# Sheet2.net
KiCad netlist of a schematic drawn in Altium Designer
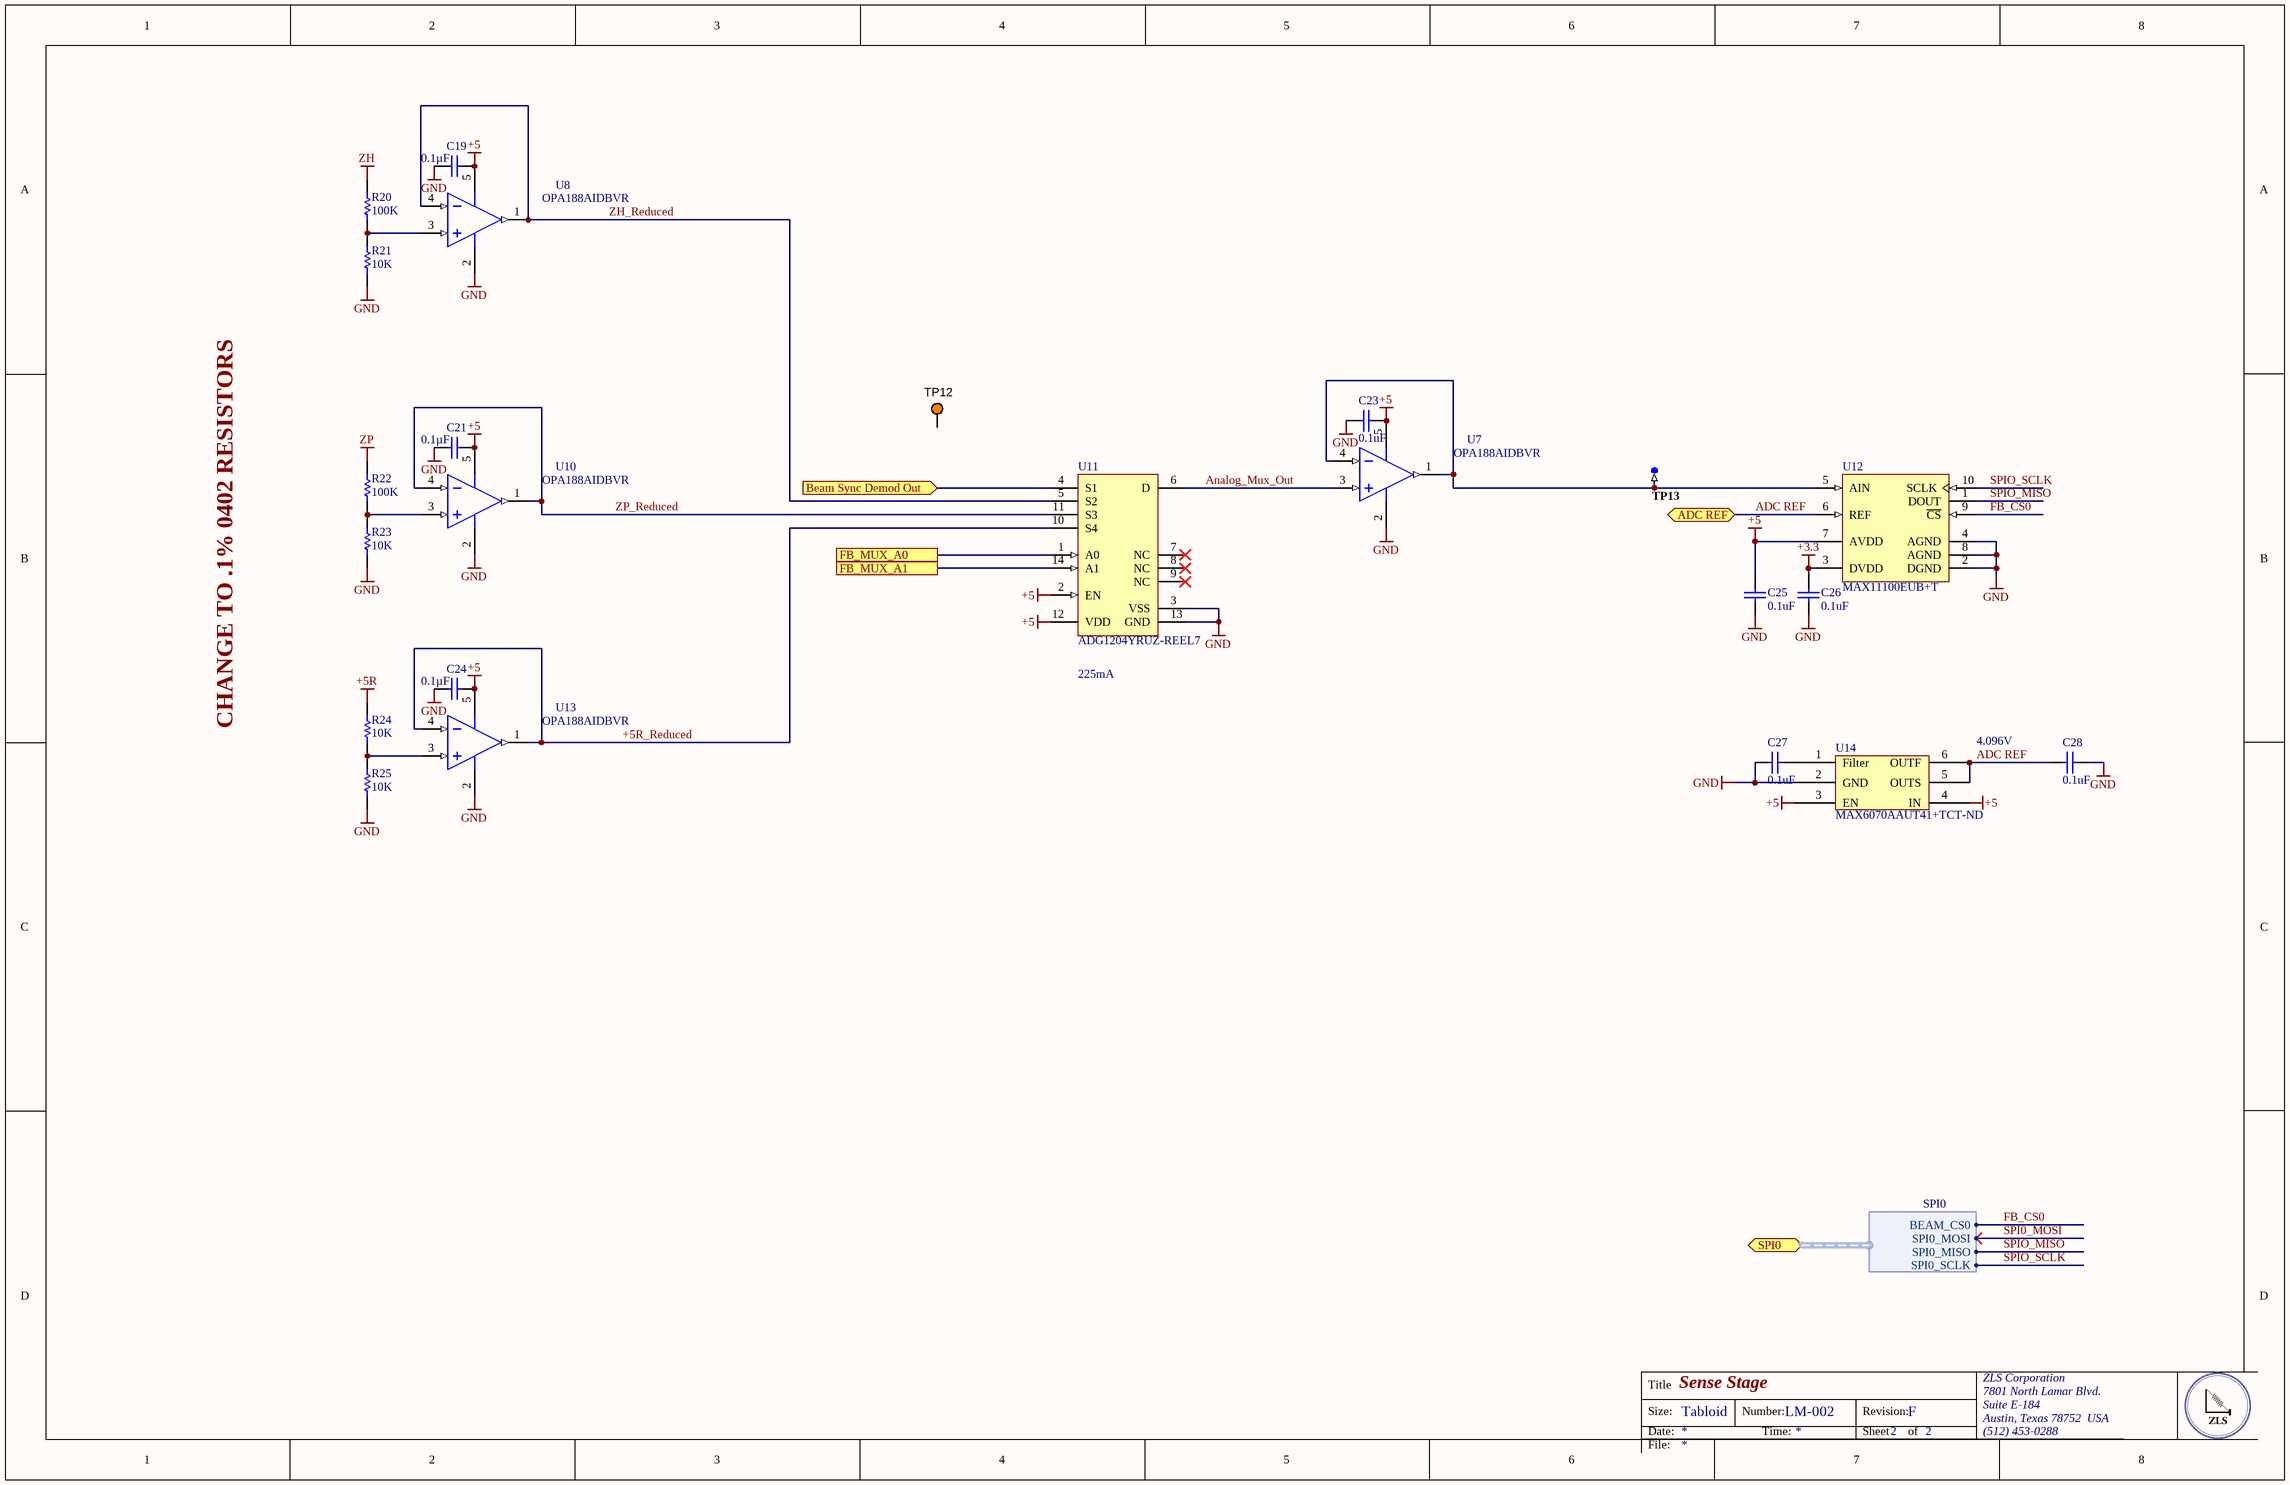
[diagram p0: Sheet2.SchDoc]

(export (version "E")
  (design (tool "Eeschema 10.0.6"))
  (components
    (comp (ref "C19")
      (value "CAP CER 0.1UF 25V X7R 0805")
      (footprint "CAPC0805(2012)145_N")
      (fields
        (field (name "MANUFACTURER") "Murata Electronics North America")
        (field (name "MANUFACTURER PART NUMBER") "GRM21BR71E104KA01L")
        (field (name "CAPACITANCE") "0.1µF")
        (field (name "TOLERANCE") "±10%")
      )
      (libsource (lib "Altium Content Vault") (part "CMP-1036-04795-1"))
    )
    (comp (ref "C21")
      (value "CAP CER 0.1UF 25V X7R 0805")
      (footprint "CAPC0805(2012)145_N")
      (fields
        (field (name "MANUFACTURER") "Murata Electronics North America")
        (field (name "MANUFACTURER PART NUMBER") "GRM21BR71E104KA01L")
        (field (name "CAPACITANCE") "0.1µF")
        (field (name "TOLERANCE") "±10%")
      )
      (libsource (lib "Altium Content Vault") (part "CMP-1036-04795-1"))
    )
    (comp (ref "C23")
      (value "0.1uF")
      (footprint "CAPC0402(1005)60_L")
      (description "CAP CER 0.1UF 10V X7R 0402")
      (fields
        (field (name "MANUFACTURER") "Murata Electronics North America")
        (field (name "MANUFACTURER PART NUMBER") "GRM155R71A104KA01D")
      )
      (libsource (lib "Altium Content Vault") (part "CMP-1034-00252-1"))
    )
    (comp (ref "C24")
      (value "CAP CER 0.1UF 25V X7R 0805")
      (footprint "CAPC0805(2012)145_N")
      (fields
        (field (name "MANUFACTURER") "Murata Electronics North America")
        (field (name "MANUFACTURER PART NUMBER") "GRM21BR71E104KA01L")
        (field (name "CAPACITANCE") "0.1µF")
        (field (name "TOLERANCE") "±10%")
      )
      (libsource (lib "Altium Content Vault") (part "CMP-1036-04795-1"))
    )
    (comp (ref "C25")
      (value "0.1uF")
      (footprint "CAPC0402(1005)60_L")
      (description "CAP CER 0.1UF 10V X7R 0402")
      (fields
        (field (name "MANUFACTURER") "Murata Electronics North America")
        (field (name "MANUFACTURER PART NUMBER") "GRM155R71A104KA01D")
      )
      (libsource (lib "Altium Content Vault") (part "CMP-1034-00252-1"))
    )
    (comp (ref "C26")
      (value "0.1uF")
      (footprint "CAPC0402(1005)60_L")
      (description "CAP CER 0.1UF 10V X7R 0402")
      (fields
        (field (name "MANUFACTURER") "Murata Electronics North America")
        (field (name "MANUFACTURER PART NUMBER") "GRM155R71A104KA01D")
      )
      (libsource (lib "Altium Content Vault") (part "CMP-1034-00252-1"))
    )
    (comp (ref "C27")
      (value "0.1uF")
      (footprint "CAPC0402(1005)60_L")
      (description "CAP CER 0.1UF 10V X7R 0402")
      (fields
        (field (name "MANUFACTURER") "Murata Electronics North America")
        (field (name "MANUFACTURER PART NUMBER") "GRM155R71A104KA01D")
      )
      (libsource (lib "Altium Content Vault") (part "CMP-1034-00252-1"))
    )
    (comp (ref "C28")
      (value "0.1uF")
      (footprint "CAPC0402(1005)60_L")
      (description "CAP CER 0.1UF 10V X7R 0402")
      (fields
        (field (name "MANUFACTURER") "Murata Electronics North America")
        (field (name "MANUFACTURER PART NUMBER") "GRM155R71A104KA01D")
      )
      (libsource (lib "Altium Content Vault") (part "CMP-1034-00252-1"))
    )
    (comp (ref "R20")
      (value "100K")
      (footprint "RESC0805(2012)_L")
      (description "RES SMD 100K OHM 1% 1/8W 0805")
      (fields
        (field (name "MANUFACTURER") "Vishay Dale")
        (field (name "MANUFACTURER PART NUMBER") "RCA0805100KFKEA")
      )
      (libsource (lib "Altium Content Vault") (part "CMP-1013-00215-1"))
    )
    (comp (ref "R21")
      (value "10K")
      (footprint "RESC0805(2012)_L")
      (description "RES SMD 10K OHM 1% 1/8W 0805")
      (fields
        (field (name "MANUFACTURER") "Vishay Dale")
        (field (name "MANUFACTURER PART NUMBER") "CRCW080510K0FKEA")
      )
      (libsource (lib "Altium Content Vault") (part "CMP-1013-00215-1"))
    )
    (comp (ref "R22")
      (value "100K")
      (footprint "RESC0805(2012)_L")
      (description "RES SMD 100K OHM 1% 1/8W 0805")
      (fields
        (field (name "MANUFACTURER") "Vishay Dale")
        (field (name "MANUFACTURER PART NUMBER") "RCA0805100KFKEA")
      )
      (libsource (lib "Altium Content Vault") (part "CMP-1013-00215-1"))
    )
    (comp (ref "R23")
      (value "10K")
      (footprint "RESC0805(2012)_L")
      (description "RES SMD 10K OHM 1% 1/8W 0805")
      (fields
        (field (name "MANUFACTURER") "Vishay Dale")
        (field (name "MANUFACTURER PART NUMBER") "CRCW080510K0FKEA")
      )
      (libsource (lib "Altium Content Vault") (part "CMP-1013-00215-1"))
    )
    (comp (ref "R24")
      (value "10K")
      (footprint "RESC0805(2012)_L")
      (description "RES SMD 10K OHM 1% 1/8W 0805")
      (fields
        (field (name "MANUFACTURER") "Vishay Dale")
        (field (name "MANUFACTURER PART NUMBER") "CRCW080510K0FKEA")
      )
      (libsource (lib "Altium Content Vault") (part "CMP-1013-00215-1"))
    )
    (comp (ref "R25")
      (value "10K")
      (footprint "RESC0805(2012)_L")
      (description "RES SMD 10K OHM 1% 1/8W 0805")
      (fields
        (field (name "MANUFACTURER") "Vishay Dale")
        (field (name "MANUFACTURER PART NUMBER") "CRCW080510K0FKEA")
      )
      (libsource (lib "Altium Content Vault") (part "CMP-1013-00215-1"))
    )
    (comp (ref "TP12")
      (value "5003")
      (footprint "KSTN-5003")
      (description "Test Point, Orange, 1-Pin THD, RoHS")
      (libsource (lib "Altium Content Vault") (part "CMP-1672-00009-1"))
    )
    (comp (ref "TP13")
      (value "TP-SM-C-100")
      (footprint "TP-SM-C-100")
      (description "Test Point, Surface Mount, Circular, Pad Diameter 1 mm")
      (fields (field (name "MANUFACTURER") "No Vendor"))
      (libsource (lib "Altium Content Vault") (part "CMP-0484-00002-2"))
    )
    (comp (ref "U7")
      (value "OPA188AIDBVR")
      (footprint "DBV0005A_M")
      (fields (field (name "MANUFACTURER") "Texas Instruments"))
      (libsource (lib "Altium Content Vault") (part "CMP-0809-00005-2"))
    )
    (comp (ref "U8")
      (value "OPA188AIDBVR")
      (footprint "DBV0005A_M")
      (fields (field (name "MANUFACTURER") "Texas Instruments"))
      (libsource (lib "Altium Content Vault") (part "CMP-0809-00005-2"))
    )
    (comp (ref "U10")
      (value "OPA188AIDBVR")
      (footprint "DBV0005A_M")
      (fields (field (name "MANUFACTURER") "Texas Instruments"))
      (libsource (lib "Altium Content Vault") (part "CMP-0809-00005-2"))
    )
    (comp (ref "U11")
      (value "ADG1204YRUZ-REEL7")
      (footprint "ADI-RU-14_L")
      (fields
        (field (name "MANUFACTURER") "Maxim Integrated")
        (field (name "MANUFACTURER PART NUMBER") "MAX11100EUB+")
        (field (name "BASE PART NUMBER") "MAX11100")
      )
      (libsource (lib "Altium Content Vault") (part "CMP-0793-00109-1"))
    )
    (comp (ref "U12")
      (value "MAX11100EUB+T")
      (footprint "U10+2_L")
      (description "16-Bit, +5V, 200ksps ADC with 10uA Shutdown, 10-Pin uMAX, -40°C to +85°C, Pb-Free, Tape and Reel")
      (fields
        (field (name "MANUFACTURER") "Maxim Integrated")
        (field (name "MANUFACTURER PART NUMBER") "MAX11100EUB+")
      )
      (libsource (lib "Altium Content Vault") (part "CMP-0249-00017-1"))
    )
    (comp (ref "U13")
      (value "OPA188AIDBVR")
      (footprint "DBV0005A_M")
      (fields (field (name "MANUFACTURER") "Texas Instruments"))
      (libsource (lib "Altium Content Vault") (part "CMP-0809-00005-2"))
    )
    (comp (ref "U14")
      (value "MAX6070AAUT41+T")
      (footprint "SOT95P280X445-6N")
      (description "IC VREF SERIES 4.096V SOT23")
      (fields
        (field (name "SUPPLIER PART NUMBER 1") "MAX6070AAUT41+TCT-ND")
        (field (name "MANUFACTURER") "Maxim Integrated")
        (field (name "TOLERANCE") "±0.04%")
      )
      (libsource (lib "ZLS_Schematic_lib") (part "MAX6070AAUT41+T"))
    )
  )
  (nets
    (net (code "2") (name "+3.3") (class "Default")
      (node (ref "C26") (pin "2") (pinfunction "2_2") (pintype "passive"))
      (node (ref "U12") (pin "3") (pinfunction "DVDD_3") (pintype "power_in"))
    )
    (net (code "3") (name "+5") (class "Default")
      (node (ref "C19") (pin "2") (pinfunction "2_2") (pintype "passive"))
      (node (ref "C21") (pin "2") (pinfunction "2_2") (pintype "passive"))
      (node (ref "C23") (pin "2") (pinfunction "2_2") (pintype "passive"))
      (node (ref "C24") (pin "2") (pinfunction "2_2") (pintype "passive"))
      (node (ref "C25") (pin "2") (pinfunction "2_2") (pintype "passive"))
      (node (ref "U10") (pin "5") (pinfunction "V+_5") (pintype "power_in"))
      (node (ref "U11") (pin "12") (pinfunction "VDD_12") (pintype "power_in"))
      (node (ref "U11") (pin "2") (pinfunction "EN_2") (pintype "input"))
      (node (ref "U12") (pin "7") (pinfunction "AVDD_7") (pintype "power_in"))
      (node (ref "U13") (pin "5") (pinfunction "V+_5") (pintype "power_in"))
      (node (ref "U14") (pin "3") (pinfunction "EN_3") (pintype "passive"))
      (node (ref "U14") (pin "4") (pinfunction "IN_4") (pintype "passive"))
      (node (ref "U7") (pin "5") (pinfunction "V+_5") (pintype "power_in"))
      (node (ref "U8") (pin "5") (pinfunction "V+_5") (pintype "power_in"))
    )
    (net (code "4") (name "+5R") (class "Default")
      (node (ref "R24") (pin "2") (pinfunction "2_2") (pintype "passive"))
    )
    (net (code "5") (name "/+5R_Reduced") (class "Default")
      (node (ref "U11") (pin "10") (pinfunction "S4_10") (pintype "passive"))
      (node (ref "U13") (pin "1") (pinfunction "OUT_1") (pintype "output"))
      (node (ref "U13") (pin "4") (pinfunction "IN-_4") (pintype "input"))
    )
    (net (code "6") (name "/ADC REF") (class "Default")
      (node (ref "C28") (pin "1") (pinfunction "1_1") (pintype "passive"))
      (node (ref "U12") (pin "6") (pinfunction "REF_6") (pintype "input"))
      (node (ref "U14") (pin "5") (pinfunction "OUTS_5") (pintype "passive"))
      (node (ref "U14") (pin "6") (pinfunction "OUTF_6") (pintype "passive"))
    )
    (net (code "7") (name "/Analog_Mux_Out") (class "Default")
      (node (ref "U11") (pin "6") (pinfunction "D_6") (pintype "passive"))
      (node (ref "U7") (pin "3") (pinfunction "IN+_3") (pintype "input"))
    )
    (net (code "8") (name "/Beam Sync Demod Out") (class "Default")
      (node (ref "U11") (pin "4") (pinfunction "S1_4") (pintype "passive"))
    )
    (net (code "9") (name "/FB_CS0") (class "Default")
      (node (ref "U12") (pin "9") (pinfunction "~{CS}_9") (pintype "input"))
    )
    (net (code "10") (name "/FB_MUX_A0") (class "Default")
      (node (ref "U11") (pin "1") (pinfunction "A0_1") (pintype "input"))
    )
    (net (code "11") (name "/FB_MUX_A1") (class "Default")
      (node (ref "U11") (pin "14") (pinfunction "A1_14") (pintype "input"))
    )
    (net (code "13") (name "/SPIO_MISO") (class "Default")
      (node (ref "U12") (pin "1") (pinfunction "DOUT_1") (pintype "tri_state"))
    )
    (net (code "14") (name "/SPIO_SCLK") (class "Default")
      (node (ref "U12") (pin "10") (pinfunction "SCLK_10") (pintype "input"))
    )
    (net (code "15") (name "/ZH_Reduced") (class "Default")
      (node (ref "U11") (pin "5") (pinfunction "S2_5") (pintype "passive"))
      (node (ref "U8") (pin "1") (pinfunction "OUT_1") (pintype "output"))
      (node (ref "U8") (pin "4") (pinfunction "IN-_4") (pintype "input"))
    )
    (net (code "16") (name "/ZP_Reduced") (class "Default")
      (node (ref "U10") (pin "1") (pinfunction "OUT_1") (pintype "output"))
      (node (ref "U10") (pin "4") (pinfunction "IN-_4") (pintype "input"))
      (node (ref "U11") (pin "11") (pinfunction "S3_11") (pintype "passive"))
    )
    (net (code "18") (name "GND") (class "Default")
      (node (ref "C19") (pin "1") (pinfunction "1_1") (pintype "passive"))
      (node (ref "C21") (pin "1") (pinfunction "1_1") (pintype "passive"))
      (node (ref "C23") (pin "1") (pinfunction "1_1") (pintype "passive"))
      (node (ref "C24") (pin "1") (pinfunction "1_1") (pintype "passive"))
      (node (ref "C25") (pin "1") (pinfunction "1_1") (pintype "passive"))
      (node (ref "C26") (pin "1") (pinfunction "1_1") (pintype "passive"))
      (node (ref "C27") (pin "1") (pinfunction "1_1") (pintype "passive"))
      (node (ref "C28") (pin "2") (pinfunction "2_2") (pintype "passive"))
      (node (ref "R21") (pin "1") (pinfunction "1_1") (pintype "passive"))
      (node (ref "R23") (pin "1") (pinfunction "1_1") (pintype "passive"))
      (node (ref "R25") (pin "1") (pinfunction "1_1") (pintype "passive"))
      (node (ref "U10") (pin "2") (pinfunction "V-_2") (pintype "power_in"))
      (node (ref "U11") (pin "13") (pinfunction "GND_13") (pintype "power_in"))
      (node (ref "U11") (pin "3") (pinfunction "VSS_3") (pintype "power_in"))
      (node (ref "U12") (pin "2") (pinfunction "DGND_2") (pintype "power_in"))
      (node (ref "U12") (pin "4") (pinfunction "AGND_4") (pintype "power_in"))
      (node (ref "U12") (pin "8") (pinfunction "AGND_8") (pintype "power_in"))
      (node (ref "U13") (pin "2") (pinfunction "V-_2") (pintype "power_in"))
      (node (ref "U14") (pin "2") (pinfunction "GND_2") (pintype "passive"))
      (node (ref "U7") (pin "2") (pinfunction "V-_2") (pintype "power_in"))
      (node (ref "U8") (pin "2") (pinfunction "V-_2") (pintype "power_in"))
    )
    (net (code "19") (name "Net-(U8-IN+)") (class "Default")
      (node (ref "R20") (pin "1") (pinfunction "1_1") (pintype "passive"))
      (node (ref "R21") (pin "2") (pinfunction "2_2") (pintype "passive"))
      (node (ref "U8") (pin "3") (pinfunction "IN+_3") (pintype "input"))
    )
    (net (code "20") (name "Net-(U10-IN+)") (class "Default")
      (node (ref "R22") (pin "1") (pinfunction "1_1") (pintype "passive"))
      (node (ref "R23") (pin "2") (pinfunction "2_2") (pintype "passive"))
      (node (ref "U10") (pin "3") (pinfunction "IN+_3") (pintype "input"))
    )
    (net (code "21") (name "Net-(U12-AIN)") (class "Default")
      (node (ref "TP13") (pin "1") (pinfunction "1_1") (pintype "input"))
      (node (ref "U12") (pin "5") (pinfunction "AIN_5") (pintype "input"))
      (node (ref "U7") (pin "1") (pinfunction "OUT_1") (pintype "output"))
      (node (ref "U7") (pin "4") (pinfunction "IN-_4") (pintype "input"))
    )
    (net (code "22") (name "Net-(U13-IN+)") (class "Default")
      (node (ref "R24") (pin "1") (pinfunction "1_1") (pintype "passive"))
      (node (ref "R25") (pin "2") (pinfunction "2_2") (pintype "passive"))
      (node (ref "U13") (pin "3") (pinfunction "IN+_3") (pintype "input"))
    )
    (net (code "23") (name "Net-(U14-Filter)") (class "Default")
      (node (ref "C27") (pin "2") (pinfunction "2_2") (pintype "passive"))
      (node (ref "U14") (pin "1") (pinfunction "Filter_1") (pintype "passive"))
    )
    (net (code "24") (name "ZH") (class "Default")
      (node (ref "R20") (pin "2") (pinfunction "2_2") (pintype "passive"))
    )
    (net (code "25") (name "ZP") (class "Default")
      (node (ref "R22") (pin "2") (pinfunction "2_2") (pintype "passive"))
    )
    (net (code "26") (name "unconnected-(TP12-Pad1)") (class "Default")
      (node (ref "TP12") (pin "1") (pinfunction "1_1") (pintype "passive"))
    )
    (net (code "27") (name "unconnected-(U11-NC-Pad7)") (class "Default")
      (node (ref "U11") (pin "7") (pinfunction "NC_7") (pintype "passive+no_connect"))
    )
    (net (code "28") (name "unconnected-(U11-NC-Pad8)") (class "Default")
      (node (ref "U11") (pin "8") (pinfunction "NC_8") (pintype "passive+no_connect"))
    )
    (net (code "29") (name "unconnected-(U11-NC-Pad9)") (class "Default")
      (node (ref "U11") (pin "9") (pinfunction "NC_9") (pintype "passive+no_connect"))
    )
  )
)
